# taczmi_sch_draft_20210426.net
KiCad netlist of a schematic drawn in Altium Designer
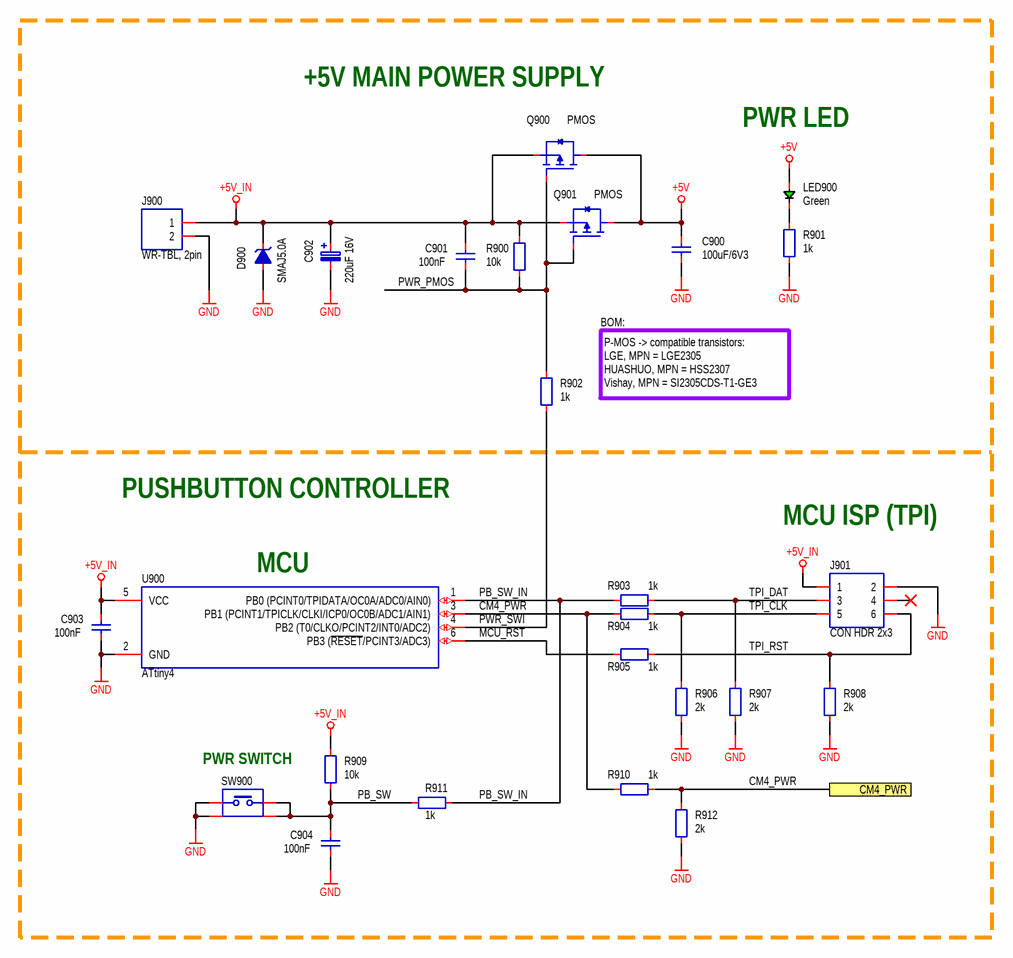
[diagram p0: taczmi_sch_draft_20210426.SchDoc]

(export (version "E")
  (design (tool "Eeschema 10.0.6"))
  (components
    (comp (ref "C900")
      (value "100uF/6V3")
      (footprint "CAP_1206_R")
      (description "Capacitor; MLCC; GENERIC; TBD; TBD; TBD; TBD; SMD; 1206 (3216);")
      (fields (field (name "MANUFACTURER") "GENERIC"))
      (libsource (lib "MirFol_db_local") (part "CAP"))
    )
    (comp (ref "C901")
      (value "100nF")
      (footprint "CAP_0603_R")
      (description "Capacitor; MLCC; 100nF; TBD; TBD; TBD; TBD; SMD; 0603 (1608);")
      (fields (field (name "MANUFACTURER") "TBD"))
      (libsource (lib "MirFol_db_local") (part "CAP"))
    )
    (comp (ref "C902")
      (value "220uF 16V")
      (footprint "CAP_RAD_D630H750P250_R")
      (description "Capacitor; Polarized;")
      (fields (field (name "MANUFACTURER") "SUNCON") (field (name "MPN") "16ME220SAX"))
      (libsource (lib "MirFol_lib") (part "CAP_POL_2P_NP"))
    )
    (comp (ref "C903")
      (value "100nF")
      (footprint "CAP_0603_R")
      (description "Capacitor; MLCC; 100nF; TBD; TBD; TBD; TBD; SMD; 0603 (1608);")
      (fields (field (name "MANUFACTURER") "TBD"))
      (libsource (lib "MirFol_db_local") (part "CAP"))
    )
    (comp (ref "C904")
      (value "100nF")
      (footprint "CAP_0603_R")
      (description "Capacitor; MLCC; 100nF; TBD; TBD; TBD; TBD; SMD; 0603 (1608);")
      (fields (field (name "MANUFACTURER") "TBD"))
      (libsource (lib "MirFol_db_local") (part "CAP"))
    )
    (comp (ref "D900")
      (value "SMAJ5.0A")
      (footprint "DIO_SMA_UNI_R")
      (description "Diode; Schottky; Unipolar;")
      (fields (field (name "MANUFACTURER") "Littelfuse"))
      (libsource (lib "MirFol_lib") (part "DIO_TVS_UNI_KA"))
    )
    (comp (ref "J900")
      (value "WR-TBL, 2pin")
      (footprint "CON_WRT_691305140002")
      (description "Connector; 1 Row;")
      (fields (field (name "MPN") "691 305 140 002") (field (name "MANUFACTURER") "Wurth Elektronik"))
      (libsource (lib "MirFol_lib") (part "CON_1X02_COL"))
    )
    (comp (ref "J901")
      (value "CON HDR 2x3")
      (description "Connector; 2 Row;")
      (libsource (lib "MirFol_lib") (part "CON_2X03_ROW"))
    )
    (comp (ref "LED900")
      (value "Green")
      (footprint "LED_0805_GRN_R")
      (description "Diode; LED; Green;")
      (libsource (lib "MirFol_lib") (part "DIO_LED_GRN"))
    )
    (comp (ref "Q900")
      (value "PMOS")
      (footprint "PKG_SOT23-3_TO236")
      (description "Transistor; PMOS;")
      (fields (field (name "MANUFACTURER") "Vishay") (field (name "MPN") "SI2305CDS-T1-GE3"))
      (libsource (lib "MirFol_lib") (part "TRA_PMOS_GSD"))
    )
    (comp (ref "Q901")
      (value "PMOS")
      (footprint "PKG_SOT23-3_TO236")
      (description "Transistor; PMOS;")
      (fields (field (name "MANUFACTURER") "Vishay") (field (name "MPN") "SI2305CDS-T1-GE3"))
      (libsource (lib "MirFol_lib") (part "TRA_PMOS_GSD"))
    )
    (comp (ref "R900")
      (value "10k")
      (footprint "RES_0603_R")
      (description "Resistor; Thick Film; 10k; 1%; 100mW; 100PPM; 75V; Standard; SMD; 0603 (1608);")
      (fields (field (name "MANUFACTURER") "Yageo Corporation") (field (name "MPN") "RC0603FR-0710KL"))
      (libsource (lib "MirFol_db_local") (part "RES"))
    )
    (comp (ref "R901")
      (value "1k")
      (footprint "RES_0603_R")
      (description "Resistor; Thick Film; 1k; 1%; 100mW; 100PPM; 75V; Standard; SMD; 0603 (1608);")
      (fields (field (name "MANUFACTURER") "Yageo Corporation") (field (name "MPN") "TBD"))
      (libsource (lib "") (part "RES_3"))
    )
    (comp (ref "R902")
      (value "1k")
      (footprint "RES_0603_R")
      (description "Resistor; Thick Film; 1k; 1%; 100mW; 100PPM; 75V; Standard; SMD; 0603 (1608);")
      (fields (field (name "MANUFACTURER") "Yageo Corporation") (field (name "MPN") "TBD"))
      (libsource (lib "MirFol_db_local") (part "RES"))
    )
    (comp (ref "R903")
      (value "1k")
      (footprint "RES_0603_R")
      (description "Resistor; Thick Film; 1k; 1%; 100mW; 100PPM; 75V; Standard; SMD; 0603 (1608);")
      (fields (field (name "MANUFACTURER") "Yageo Corporation") (field (name "MPN") "TBD"))
      (libsource (lib "") (part "RES_2"))
    )
    (comp (ref "R904")
      (value "1k")
      (footprint "RES_0603_R")
      (description "Resistor; Thick Film; 1k; 1%; 100mW; 100PPM; 75V; Standard; SMD; 0603 (1608);")
      (fields (field (name "MANUFACTURER") "Yageo Corporation") (field (name "MPN") "TBD"))
      (libsource (lib "") (part "RES_2"))
    )
    (comp (ref "R905")
      (value "1k")
      (footprint "RES_0603_R")
      (description "Resistor; Thick Film; 1k; 1%; 100mW; 100PPM; 75V; Standard; SMD; 0603 (1608);")
      (fields (field (name "MANUFACTURER") "Yageo Corporation") (field (name "MPN") "TBD"))
      (libsource (lib "") (part "RES_2"))
    )
    (comp (ref "R906")
      (value "2k")
      (footprint "RES_0603_R")
      (description "Resistor; Thick Film; 2k2; 1%; 100mW; 100PPM; 75V; Standard; SMD; 0603 (1608);")
      (fields (field (name "MANUFACTURER") "Yageo Corporation") (field (name "MPN") "TBD"))
      (libsource (lib "MirFol_db_local") (part "RES"))
    )
    (comp (ref "R907")
      (value "2k")
      (footprint "RES_0603_R")
      (description "Resistor; Thick Film; 2k2; 1%; 100mW; 100PPM; 75V; Standard; SMD; 0603 (1608);")
      (fields (field (name "MANUFACTURER") "Yageo Corporation") (field (name "MPN") "TBD"))
      (libsource (lib "MirFol_db_local") (part "RES"))
    )
    (comp (ref "R908")
      (value "2k")
      (footprint "RES_0603_R")
      (description "Resistor; Thick Film; 2k2; 1%; 100mW; 100PPM; 75V; Standard; SMD; 0603 (1608);")
      (fields (field (name "MANUFACTURER") "Yageo Corporation") (field (name "MPN") "TBD"))
      (libsource (lib "MirFol_db_local") (part "RES"))
    )
    (comp (ref "R909")
      (value "10k")
      (footprint "RES_0603_R")
      (description "Resistor; Thick Film; 10k; 1%; 100mW; 100PPM; 75V; Standard; SMD; 0603 (1608);")
      (fields (field (name "MANUFACTURER") "Yageo Corporation") (field (name "MPN") "RC0603FR-0710KL"))
      (libsource (lib "MirFol_db_local") (part "RES"))
    )
    (comp (ref "R910")
      (value "1k")
      (footprint "RES_0603_R")
      (description "Resistor; Thick Film; 1k; 1%; 100mW; 100PPM; 75V; Standard; SMD; 0603 (1608);")
      (fields (field (name "MANUFACTURER") "Yageo Corporation") (field (name "MPN") "TBD"))
      (libsource (lib "") (part "RES_2"))
    )
    (comp (ref "R911")
      (value "1k")
      (footprint "RES_0603_R")
      (description "Resistor; Thick Film; 1k; 1%; 100mW; 100PPM; 75V; Standard; SMD; 0603 (1608);")
      (fields (field (name "MANUFACTURER") "Yageo Corporation") (field (name "MPN") "TBD"))
      (libsource (lib "") (part "RES_1"))
    )
    (comp (ref "R912")
      (value "2k")
      (footprint "RES_0603_R")
      (description "Resistor; Thick Film; 2k2; 1%; 100mW; 100PPM; 75V; Standard; SMD; 0603 (1608);")
      (fields (field (name "MANUFACTURER") "Yageo Corporation") (field (name "MPN") "TBD"))
      (libsource (lib "MirFol_db_local") (part "RES"))
    )
    (comp (ref "SW900")
      (value "~")
      (description "Switch; Tactile; Monostable; Shielded;")
      (libsource (lib "MirFol_lib") (part "SWI_TACT_2P_SH"))
    )
    (comp (ref "U900")
      (value "ATtiny4")
      (footprint "PKG_SOT23-6")
      (description "ICC; MCU;")
      (fields (field (name "MANUFACTURER") "Microchip Technology") (field (name "MPN") "ATTINY4-TSHR"))
      (libsource (lib "MirFol_lib") (part "ICC_MCP_ATTINY4_5_8_9_SOT-23"))
    )
  )
  (nets
    (net (code "1") (name "+5V") (class "Default")
      (node (ref "C900") (pin "2") (pintype "passive"))
      (node (ref "LED900") (pin "2") (pinfunction "2_2") (pintype "passive"))
      (node (ref "Q900") (pin "3") (pinfunction "D_3") (pintype "passive"))
      (node (ref "Q901") (pin "3") (pinfunction "D_3") (pintype "passive"))
    )
    (net (code "2") (name "+5V_IN") (class "Default")
      (node (ref "C901") (pin "2") (pintype "passive"))
      (node (ref "C902") (pin "2") (pintype "passive"))
      (node (ref "C903") (pin "2") (pintype "passive"))
      (node (ref "D900") (pin "1") (pinfunction "K_1") (pintype "passive"))
      (node (ref "J900") (pin "1") (pinfunction "1_1") (pintype "passive"))
      (node (ref "J901") (pin "1") (pinfunction "1_1") (pintype "passive"))
      (node (ref "Q900") (pin "2") (pinfunction "S_2") (pintype "passive"))
      (node (ref "Q901") (pin "2") (pinfunction "S_2") (pintype "passive"))
      (node (ref "R900") (pin "2") (pinfunction "2_2") (pintype "passive"))
      (node (ref "R909") (pin "2") (pinfunction "2_2") (pintype "passive"))
      (node (ref "U900") (pin "5") (pinfunction "VCC_5") (pintype "power_in"))
    )
    (net (code "3") (name "/CM4_PWR") (class "Default")
      (node (ref "R904") (pin "2") (pinfunction "2_2") (pintype "passive"))
      (node (ref "R910") (pin "1") (pinfunction "1_1") (pintype "passive"))
      (node (ref "R910") (pin "2") (pinfunction "2_2") (pintype "passive"))
      (node (ref "R912") (pin "2") (pinfunction "2_2") (pintype "passive"))
      (node (ref "U900") (pin "3") (pinfunction "PB1_(PCINT1/TPICLK/CLKI/ICP0/OC0B/ADC1/AIN1)_3") (pintype "bidirectional"))
    )
    (net (code "4") (name "/MCU_RST") (class "Default")
      (node (ref "R905") (pin "2") (pinfunction "2_2") (pintype "passive"))
      (node (ref "U900") (pin "6") (pinfunction "PB3_(~{RESET}/PCINT3/ADC3)_6") (pintype "bidirectional"))
    )
    (net (code "5") (name "/PB_SW") (class "Default")
      (node (ref "C904") (pin "2") (pintype "passive"))
      (node (ref "R909") (pin "1") (pinfunction "1_1") (pintype "passive"))
      (node (ref "R911") (pin "1") (pinfunction "1_1") (pintype "passive"))
      (node (ref "SW900") (pin "2") (pinfunction "SW2_2") (pintype "passive"))
      (node (ref "SW900") (pin "4") (pinfunction "FRM2_4") (pintype "passive"))
    )
    (net (code "6") (name "/PB_SW_IN") (class "Default")
      (node (ref "R903") (pin "2") (pinfunction "2_2") (pintype "passive"))
      (node (ref "R911") (pin "2") (pinfunction "2_2") (pintype "passive"))
      (node (ref "U900") (pin "1") (pinfunction "PB0_(PCINT0/TPIDATA/OC0A/ADC0/AIN0)_1") (pintype "bidirectional"))
    )
    (net (code "7") (name "/PWR_PMOS") (class "Default")
      (node (ref "C901") (pin "1") (pintype "passive"))
      (node (ref "Q900") (pin "1") (pinfunction "G_1") (pintype "passive"))
      (node (ref "Q901") (pin "1") (pinfunction "G_1") (pintype "passive"))
      (node (ref "R900") (pin "1") (pinfunction "1_1") (pintype "passive"))
      (node (ref "R902") (pin "2") (pinfunction "2_2") (pintype "passive"))
    )
    (net (code "8") (name "/PWR_SWI") (class "Default")
      (node (ref "R902") (pin "1") (pinfunction "1_1") (pintype "passive"))
      (node (ref "U900") (pin "4") (pinfunction "PB2_(T0/CLKO/PCINT2/INT0/ADC2)_4") (pintype "bidirectional"))
    )
    (net (code "9") (name "/TPI_CLK") (class "Default")
      (node (ref "J901") (pin "5") (pinfunction "5_5") (pintype "passive"))
      (node (ref "R904") (pin "1") (pinfunction "1_1") (pintype "passive"))
      (node (ref "R906") (pin "2") (pinfunction "2_2") (pintype "passive"))
    )
    (net (code "10") (name "/TPI_DAT") (class "Default")
      (node (ref "J901") (pin "3") (pinfunction "3_3") (pintype "passive"))
      (node (ref "R903") (pin "1") (pinfunction "1_1") (pintype "passive"))
      (node (ref "R907") (pin "2") (pinfunction "2_2") (pintype "passive"))
    )
    (net (code "11") (name "/TPI_RST") (class "Default")
      (node (ref "J901") (pin "6") (pinfunction "6_6") (pintype "passive"))
      (node (ref "R905") (pin "1") (pinfunction "1_1") (pintype "passive"))
      (node (ref "R908") (pin "2") (pinfunction "2_2") (pintype "passive"))
    )
    (net (code "12") (name "GND") (class "Default")
      (node (ref "C900") (pin "1") (pintype "passive"))
      (node (ref "C902") (pin "1") (pintype "passive"))
      (node (ref "C903") (pin "1") (pintype "passive"))
      (node (ref "C904") (pin "1") (pintype "passive"))
      (node (ref "D900") (pin "2") (pinfunction "A_2") (pintype "passive"))
      (node (ref "J900") (pin "2") (pinfunction "2_2") (pintype "passive"))
      (node (ref "J901") (pin "2") (pinfunction "2_2") (pintype "passive"))
      (node (ref "R901") (pin "2") (pinfunction "2_2") (pintype "passive"))
      (node (ref "R906") (pin "1") (pinfunction "1_1") (pintype "passive"))
      (node (ref "R907") (pin "1") (pinfunction "1_1") (pintype "passive"))
      (node (ref "R908") (pin "1") (pinfunction "1_1") (pintype "passive"))
      (node (ref "R912") (pin "1") (pinfunction "1_1") (pintype "passive"))
      (node (ref "SW900") (pin "1") (pinfunction "SW1_1") (pintype "passive"))
      (node (ref "SW900") (pin "3") (pinfunction "FRM1_3") (pintype "passive"))
      (node (ref "U900") (pin "2") (pinfunction "GND_2") (pintype "power_in"))
    )
    (net (code "13") (name "Net-(LED900-Pad1)") (class "Default")
      (node (ref "LED900") (pin "1") (pinfunction "1_1") (pintype "passive"))
      (node (ref "R901") (pin "1") (pinfunction "1_1") (pintype "passive"))
    )
    (net (code "14") (name "unconnected-(J901-Pad4)") (class "Default")
      (node (ref "J901") (pin "4") (pinfunction "4_4") (pintype "passive+no_connect"))
    )
  )
)
